# RJ45.net
KiCad netlist of a schematic drawn in Altium Designer
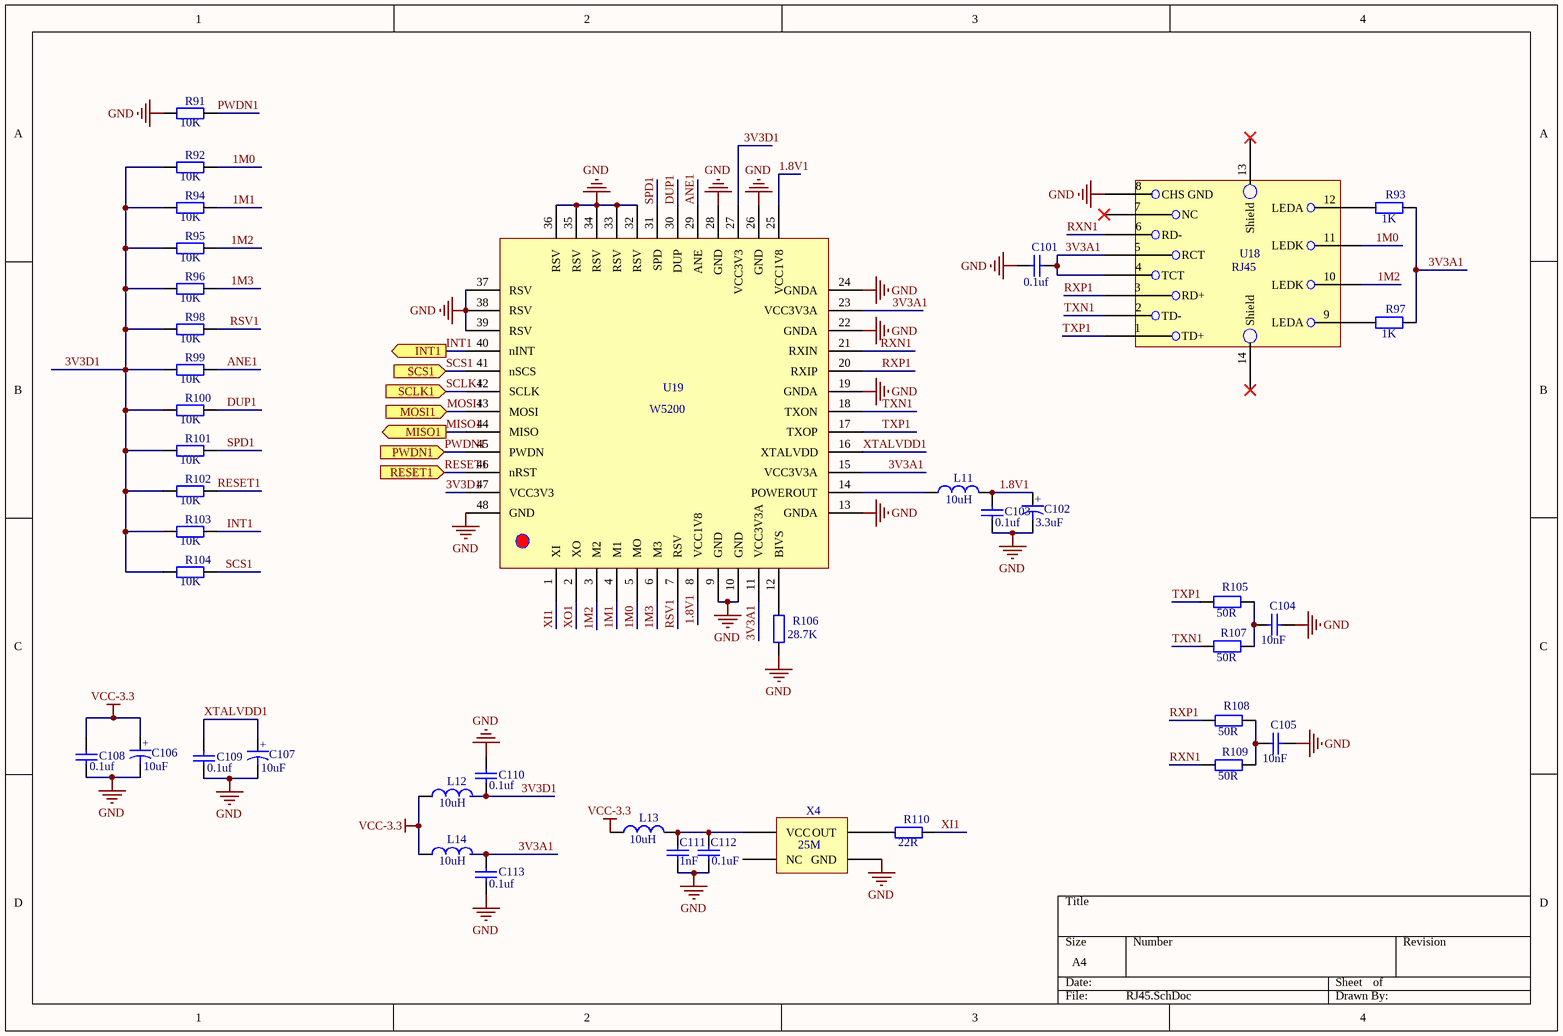
[diagram p0: RJ45.SchDoc]

(export (version "E")
  (design (tool "Eeschema 10.0.6"))
  (components
    (comp (ref "C101")
      (value "0.1uf")
      (footprint "0603")
      (fields (field (name "Comment") "Capacitor-0603"))
      (libsource (lib "原理图库") (part "Capacitor-0603"))
    )
    (comp (ref "C102")
      (value "3.3uF")
      (footprint "钽电容1206（A3216）")
      (fields (field (name "ALTIUM_UNNAMED_1") "+") (field (name "Comment") "电解电容"))
      (libsource (lib "原理图库") (part "电解电容"))
    )
    (comp (ref "C103")
      (value "0.1uf")
      (footprint "0603")
      (fields (field (name "Comment") "Capacitor-0603"))
      (libsource (lib "原理图库") (part "Capacitor-0603"))
    )
    (comp (ref "C104")
      (value "10nF")
      (footprint "0603")
      (fields (field (name "Comment") "Capacitor-0603"))
      (libsource (lib "原理图库") (part "Capacitor-0603"))
    )
    (comp (ref "C105")
      (value "10nF")
      (footprint "0603")
      (fields (field (name "Comment") "Capacitor-0603"))
      (libsource (lib "原理图库") (part "Capacitor-0603"))
    )
    (comp (ref "C106")
      (value "10uF")
      (footprint "钽电容1206（A3216）")
      (fields (field (name "ALTIUM_UNNAMED_1") "+") (field (name "Comment") "电解电容"))
      (libsource (lib "原理图库") (part "电解电容"))
    )
    (comp (ref "C107")
      (value "10uF")
      (footprint "钽电容1206（A3216）")
      (fields (field (name "ALTIUM_UNNAMED_1") "+") (field (name "Comment") "电解电容"))
      (libsource (lib "原理图库") (part "电解电容"))
    )
    (comp (ref "C108")
      (value "0.1uf")
      (footprint "0603")
      (fields (field (name "Comment") "Capacitor-0603"))
      (libsource (lib "原理图库") (part "Capacitor-0603"))
    )
    (comp (ref "C109")
      (value "0.1uf")
      (footprint "0603")
      (fields (field (name "Comment") "Capacitor-0603"))
      (libsource (lib "原理图库") (part "Capacitor-0603"))
    )
    (comp (ref "C110")
      (value "0.1uf")
      (footprint "0603")
      (fields (field (name "Comment") "Capacitor-0603"))
      (libsource (lib "原理图库") (part "Capacitor-0603"))
    )
    (comp (ref "C111")
      (value "1nF")
      (footprint "0603")
      (fields (field (name "Comment") "Capacitor-0603"))
      (libsource (lib "原理图库") (part "Capacitor-0603"))
    )
    (comp (ref "C112")
      (value "0.1uF")
      (footprint "0603")
      (fields (field (name "Comment") "Capacitor-0603"))
      (libsource (lib "原理图库") (part "Capacitor-0603"))
    )
    (comp (ref "C113")
      (value "0.1uf")
      (footprint "0603")
      (fields (field (name "Comment") "Capacitor-0603"))
      (libsource (lib "原理图库") (part "Capacitor-0603"))
    )
    (comp (ref "L11")
      (value "10uH")
      (footprint "0805")
      (fields (field (name "Comment") "Inductor"))
      (libsource (lib "原理图库") (part "Inductor"))
    )
    (comp (ref "L12")
      (value "10uH")
      (footprint "0805")
      (fields (field (name "Comment") "Inductor"))
      (libsource (lib "原理图库") (part "Inductor"))
    )
    (comp (ref "L13")
      (value "10uH")
      (footprint "0805")
      (fields (field (name "Comment") "Inductor"))
      (libsource (lib "原理图库") (part "Inductor"))
    )
    (comp (ref "L14")
      (value "10uH")
      (footprint "0805")
      (fields (field (name "Comment") "Inductor"))
      (libsource (lib "原理图库") (part "Inductor"))
    )
    (comp (ref "R91")
      (value "10K")
      (footprint "0603")
      (fields (field (name "Comment") "Resistor-0603"))
      (libsource (lib "原理图库") (part "Resistor-0603"))
    )
    (comp (ref "R92")
      (value "10K")
      (footprint "0603")
      (fields (field (name "Comment") "Resistor-0603"))
      (libsource (lib "原理图库") (part "Resistor-0603"))
    )
    (comp (ref "R93")
      (value "1K")
      (footprint "0603")
      (fields (field (name "Comment") "Resistor-0603"))
      (libsource (lib "原理图库") (part "Resistor-0603"))
    )
    (comp (ref "R94")
      (value "10K")
      (footprint "0603")
      (fields (field (name "Comment") "Resistor-0603"))
      (libsource (lib "原理图库") (part "Resistor-0603"))
    )
    (comp (ref "R95")
      (value "10K")
      (footprint "0603")
      (fields (field (name "Comment") "Resistor-0603"))
      (libsource (lib "原理图库") (part "Resistor-0603"))
    )
    (comp (ref "R96")
      (value "10K")
      (footprint "0603")
      (fields (field (name "Comment") "Resistor-0603"))
      (libsource (lib "原理图库") (part "Resistor-0603"))
    )
    (comp (ref "R97")
      (value "1K")
      (footprint "0603")
      (fields (field (name "Comment") "Resistor-0603"))
      (libsource (lib "原理图库") (part "Resistor-0603"))
    )
    (comp (ref "R98")
      (value "10K")
      (footprint "0603")
      (fields (field (name "Comment") "Resistor-0603"))
      (libsource (lib "原理图库") (part "Resistor-0603"))
    )
    (comp (ref "R99")
      (value "10K")
      (footprint "0603")
      (fields (field (name "Comment") "Resistor-0603"))
      (libsource (lib "原理图库") (part "Resistor-0603"))
    )
    (comp (ref "R100")
      (value "10K")
      (footprint "0603")
      (fields (field (name "Comment") "Resistor-0603"))
      (libsource (lib "原理图库") (part "Resistor-0603"))
    )
    (comp (ref "R101")
      (value "10K")
      (footprint "0603")
      (fields (field (name "Comment") "Resistor-0603"))
      (libsource (lib "原理图库") (part "Resistor-0603"))
    )
    (comp (ref "R102")
      (value "10K")
      (footprint "0603")
      (fields (field (name "Comment") "Resistor-0603"))
      (libsource (lib "原理图库") (part "Resistor-0603"))
    )
    (comp (ref "R103")
      (value "10K")
      (footprint "0603")
      (fields (field (name "Comment") "Resistor-0603"))
      (libsource (lib "原理图库") (part "Resistor-0603"))
    )
    (comp (ref "R104")
      (value "10K")
      (footprint "0603")
      (fields (field (name "Comment") "Resistor-0603"))
      (libsource (lib "原理图库") (part "Resistor-0603"))
    )
    (comp (ref "R105")
      (value "50R")
      (footprint "0603")
      (fields (field (name "Comment") "Resistor-0603"))
      (libsource (lib "原理图库") (part "Resistor-0603"))
    )
    (comp (ref "R106")
      (value "28.7K")
      (footprint "0603")
      (fields (field (name "Comment") "Resistor-0603"))
      (libsource (lib "") (part "Resistor-0603_1"))
    )
    (comp (ref "R107")
      (value "50R")
      (footprint "0603")
      (fields (field (name "Comment") "Resistor-0603"))
      (libsource (lib "原理图库") (part "Resistor-0603"))
    )
    (comp (ref "R108")
      (value "50R")
      (footprint "0603")
      (fields (field (name "Comment") "Resistor-0603"))
      (libsource (lib "原理图库") (part "Resistor-0603"))
    )
    (comp (ref "R109")
      (value "50R")
      (footprint "0603")
      (fields (field (name "Comment") "Resistor-0603"))
      (libsource (lib "原理图库") (part "Resistor-0603"))
    )
    (comp (ref "R110")
      (value "22R")
      (footprint "0603")
      (fields (field (name "Comment") "Resistor-0603"))
      (libsource (lib "原理图库") (part "Resistor-0603"))
    )
    (comp (ref "U18")
      (value "RJ45")
      (footprint "RJ45")
      (fields (field (name "NAME") "RJ45"))
      (libsource (lib "原理图库") (part "RJ45"))
    )
    (comp (ref "U19")
      (value "W5200-Chip")
      (footprint "W5200-Chip")
      (fields (field (name "NAME") "W5200"))
      (libsource (lib "原理图库") (part "W5200-Chip"))
    )
    (comp (ref "X4")
      (value "25M")
      (footprint "有源晶振7050")
      (fields (field (name "Comment") "有源晶振"))
      (libsource (lib "原理图库") (part "有源晶振"))
    )
  )
  (nets
    (net (code "1") (name "/1.8V1") (class "Default")
      (node (ref "C102") (pin "2") (pinfunction "2_2") (pintype "passive"))
      (node (ref "C103") (pin "2") (pinfunction "2_2") (pintype "passive"))
      (node (ref "L11") (pin "2") (pinfunction "2_2") (pintype "passive"))
      (node (ref "U19") (pin "25") (pinfunction "VCC1V8_25") (pintype "passive"))
      (node (ref "U19") (pin "8") (pinfunction "VCC1V8_8") (pintype "passive"))
    )
    (net (code "2") (name "/1M0") (class "Default")
      (node (ref "R92") (pin "2") (pinfunction "2_2") (pintype "passive"))
      (node (ref "U18") (pin "11") (pinfunction "LEDK_11") (pintype "passive"))
      (node (ref "U19") (pin "5") (pinfunction "MO_5") (pintype "passive"))
    )
    (net (code "3") (name "/1M1") (class "Default")
      (node (ref "R94") (pin "2") (pinfunction "2_2") (pintype "passive"))
      (node (ref "U19") (pin "4") (pinfunction "M1_4") (pintype "passive"))
    )
    (net (code "4") (name "/1M2") (class "Default")
      (node (ref "R95") (pin "2") (pinfunction "2_2") (pintype "passive"))
      (node (ref "U18") (pin "10") (pinfunction "LEDK_10") (pintype "passive"))
      (node (ref "U19") (pin "3") (pinfunction "M2_3") (pintype "passive"))
    )
    (net (code "5") (name "/1M3") (class "Default")
      (node (ref "R96") (pin "2") (pinfunction "2_2") (pintype "passive"))
      (node (ref "U19") (pin "6") (pinfunction "M3_6") (pintype "passive"))
    )
    (net (code "6") (name "/3V3A1") (class "Default")
      (node (ref "C101") (pin "1") (pinfunction "1_1") (pintype "passive"))
      (node (ref "C113") (pin "1") (pinfunction "1_1") (pintype "passive"))
      (node (ref "L14") (pin "2") (pinfunction "2_2") (pintype "passive"))
      (node (ref "R93") (pin "2") (pinfunction "2_2") (pintype "passive"))
      (node (ref "R97") (pin "2") (pinfunction "2_2") (pintype "passive"))
      (node (ref "U18") (pin "4") (pinfunction "TCT_4") (pintype "passive"))
      (node (ref "U18") (pin "5") (pinfunction "RCT_5") (pintype "passive"))
      (node (ref "U19") (pin "11") (pinfunction "VCC3V3A_11") (pintype "passive"))
      (node (ref "U19") (pin "15") (pinfunction "VCC3V3A_15") (pintype "passive"))
      (node (ref "U19") (pin "23") (pinfunction "VCC3V3A_23") (pintype "passive"))
    )
    (net (code "7") (name "/3V3D1") (class "Default")
      (node (ref "C110") (pin "1") (pinfunction "1_1") (pintype "passive"))
      (node (ref "L12") (pin "2") (pinfunction "2_2") (pintype "passive"))
      (node (ref "R100") (pin "1") (pinfunction "1_1") (pintype "passive"))
      (node (ref "R101") (pin "1") (pinfunction "1_1") (pintype "passive"))
      (node (ref "R102") (pin "1") (pinfunction "1_1") (pintype "passive"))
      (node (ref "R103") (pin "1") (pinfunction "1_1") (pintype "passive"))
      (node (ref "R104") (pin "1") (pinfunction "1_1") (pintype "passive"))
      (node (ref "R92") (pin "1") (pinfunction "1_1") (pintype "passive"))
      (node (ref "R94") (pin "1") (pinfunction "1_1") (pintype "passive"))
      (node (ref "R95") (pin "1") (pinfunction "1_1") (pintype "passive"))
      (node (ref "R96") (pin "1") (pinfunction "1_1") (pintype "passive"))
      (node (ref "R98") (pin "1") (pinfunction "1_1") (pintype "passive"))
      (node (ref "R99") (pin "1") (pinfunction "1_1") (pintype "passive"))
      (node (ref "U19") (pin "27") (pinfunction "VCC3V3_27") (pintype "passive"))
      (node (ref "U19") (pin "47") (pinfunction "VCC3V3_47") (pintype "passive"))
    )
    (net (code "8") (name "/ANE1") (class "Default")
      (node (ref "R99") (pin "2") (pinfunction "2_2") (pintype "passive"))
      (node (ref "U19") (pin "29") (pinfunction "ANE_29") (pintype "passive"))
    )
    (net (code "9") (name "/DUP1") (class "Default")
      (node (ref "R100") (pin "2") (pinfunction "2_2") (pintype "passive"))
      (node (ref "U19") (pin "30") (pinfunction "DUP_30") (pintype "passive"))
    )
    (net (code "10") (name "/INT1") (class "Default")
      (node (ref "R103") (pin "2") (pinfunction "2_2") (pintype "passive"))
      (node (ref "U19") (pin "40") (pinfunction "nINT_40") (pintype "passive"))
    )
    (net (code "11") (name "/MISO1") (class "Default")
      (node (ref "U19") (pin "44") (pinfunction "MISO_44") (pintype "passive"))
    )
    (net (code "12") (name "/MOSI1") (class "Default")
      (node (ref "U19") (pin "43") (pinfunction "MOSI_43") (pintype "passive"))
    )
    (net (code "13") (name "/PWDN1") (class "Default")
      (node (ref "R91") (pin "2") (pinfunction "2_2") (pintype "passive"))
      (node (ref "U19") (pin "45") (pinfunction "PWDN_45") (pintype "passive"))
    )
    (net (code "14") (name "/RESET1") (class "Default")
      (node (ref "R102") (pin "2") (pinfunction "2_2") (pintype "passive"))
      (node (ref "U19") (pin "46") (pinfunction "nRST_46") (pintype "passive"))
    )
    (net (code "15") (name "/RSV1") (class "Default")
      (node (ref "R98") (pin "2") (pinfunction "2_2") (pintype "passive"))
      (node (ref "U19") (pin "7") (pinfunction "RSV_7") (pintype "passive"))
    )
    (net (code "16") (name "/RXN1") (class "Default")
      (node (ref "R109") (pin "1") (pinfunction "1_1") (pintype "passive"))
      (node (ref "U18") (pin "6") (pinfunction "RD-_6") (pintype "passive"))
      (node (ref "U19") (pin "21") (pinfunction "RXIN_21") (pintype "passive"))
    )
    (net (code "17") (name "/RXP1") (class "Default")
      (node (ref "R108") (pin "1") (pinfunction "1_1") (pintype "passive"))
      (node (ref "U18") (pin "3") (pinfunction "RD+_3") (pintype "passive"))
      (node (ref "U19") (pin "20") (pinfunction "RXIP_20") (pintype "passive"))
    )
    (net (code "18") (name "/SCLK1") (class "Default")
      (node (ref "U19") (pin "42") (pinfunction "SCLK_42") (pintype "passive"))
    )
    (net (code "19") (name "/SCS1") (class "Default")
      (node (ref "R104") (pin "2") (pinfunction "2_2") (pintype "passive"))
      (node (ref "U19") (pin "41") (pinfunction "nSCS_41") (pintype "passive"))
    )
    (net (code "20") (name "/SPD1") (class "Default")
      (node (ref "R101") (pin "2") (pinfunction "2_2") (pintype "passive"))
      (node (ref "U19") (pin "31") (pinfunction "SPD_31") (pintype "passive"))
    )
    (net (code "21") (name "/TXN1") (class "Default")
      (node (ref "R107") (pin "1") (pinfunction "1_1") (pintype "passive"))
      (node (ref "U18") (pin "2") (pinfunction "TD-_2") (pintype "passive"))
      (node (ref "U19") (pin "18") (pinfunction "TXON_18") (pintype "passive"))
    )
    (net (code "22") (name "/TXP1") (class "Default")
      (node (ref "R105") (pin "1") (pinfunction "1_1") (pintype "passive"))
      (node (ref "U18") (pin "1") (pinfunction "TD+_1") (pintype "passive"))
      (node (ref "U19") (pin "17") (pinfunction "TXOP_17") (pintype "passive"))
    )
    (net (code "23") (name "/XI1") (class "Default")
      (node (ref "R110") (pin "2") (pinfunction "2_2") (pintype "passive"))
      (node (ref "U19") (pin "1") (pinfunction "XI_1") (pintype "passive"))
    )
    (net (code "24") (name "/XO1") (class "Default")
      (node (ref "U19") (pin "2") (pinfunction "XO_2") (pintype "passive"))
    )
    (net (code "25") (name "/XTALVDD1") (class "Default")
      (node (ref "C107") (pin "2") (pinfunction "2_2") (pintype "passive"))
      (node (ref "C109") (pin "2") (pinfunction "2_2") (pintype "passive"))
      (node (ref "U19") (pin "16") (pinfunction "XTALVDD_16") (pintype "passive"))
    )
    (net (code "26") (name "GND") (class "Default")
      (node (ref "C101") (pin "2") (pinfunction "2_2") (pintype "passive"))
      (node (ref "C102") (pin "1") (pinfunction "1_1") (pintype "passive"))
      (node (ref "C103") (pin "1") (pinfunction "1_1") (pintype "passive"))
      (node (ref "C104") (pin "2") (pinfunction "2_2") (pintype "passive"))
      (node (ref "C105") (pin "2") (pinfunction "2_2") (pintype "passive"))
      (node (ref "C106") (pin "1") (pinfunction "1_1") (pintype "passive"))
      (node (ref "C107") (pin "1") (pinfunction "1_1") (pintype "passive"))
      (node (ref "C108") (pin "1") (pinfunction "1_1") (pintype "passive"))
      (node (ref "C109") (pin "1") (pinfunction "1_1") (pintype "passive"))
      (node (ref "C110") (pin "2") (pinfunction "2_2") (pintype "passive"))
      (node (ref "C111") (pin "2") (pinfunction "2_2") (pintype "passive"))
      (node (ref "C112") (pin "2") (pinfunction "2_2") (pintype "passive"))
      (node (ref "C113") (pin "2") (pinfunction "2_2") (pintype "passive"))
      (node (ref "R106") (pin "1") (pinfunction "1_1") (pintype "passive"))
      (node (ref "R91") (pin "1") (pinfunction "1_1") (pintype "passive"))
      (node (ref "U18") (pin "8") (pinfunction "CHS_GND_8") (pintype "passive"))
      (node (ref "U19") (pin "10") (pinfunction "GND_10") (pintype "passive"))
      (node (ref "U19") (pin "13") (pinfunction "GNDA_13") (pintype "passive"))
      (node (ref "U19") (pin "19") (pinfunction "GNDA_19") (pintype "passive"))
      (node (ref "U19") (pin "22") (pinfunction "GNDA_22") (pintype "passive"))
      (node (ref "U19") (pin "24") (pinfunction "GNDA_24") (pintype "passive"))
      (node (ref "U19") (pin "26") (pinfunction "GND_26") (pintype "passive"))
      (node (ref "U19") (pin "28") (pinfunction "GND_28") (pintype "passive"))
      (node (ref "U19") (pin "32") (pinfunction "RSV_32") (pintype "passive"))
      (node (ref "U19") (pin "33") (pinfunction "RSV_33") (pintype "passive"))
      (node (ref "U19") (pin "34") (pinfunction "RSV_34") (pintype "passive"))
      (node (ref "U19") (pin "35") (pinfunction "RSV_35") (pintype "passive"))
      (node (ref "U19") (pin "36") (pinfunction "RSV_36") (pintype "passive"))
      (node (ref "U19") (pin "37") (pinfunction "RSV_37") (pintype "passive"))
      (node (ref "U19") (pin "38") (pinfunction "RSV_38") (pintype "passive"))
      (node (ref "U19") (pin "39") (pinfunction "RSV_39") (pintype "passive"))
      (node (ref "U19") (pin "48") (pinfunction "GND_48") (pintype "passive"))
      (node (ref "U19") (pin "9") (pinfunction "GND_9") (pintype "passive"))
      (node (ref "X4") (pin "2") (pinfunction "GND_2") (pintype "passive"))
    )
    (net (code "27") (name "Net-(C104-Pad1)") (class "Default")
      (node (ref "C104") (pin "1") (pinfunction "1_1") (pintype "passive"))
      (node (ref "R105") (pin "2") (pinfunction "2_2") (pintype "passive"))
      (node (ref "R107") (pin "2") (pinfunction "2_2") (pintype "passive"))
    )
    (net (code "28") (name "Net-(C105-Pad1)") (class "Default")
      (node (ref "C105") (pin "1") (pinfunction "1_1") (pintype "passive"))
      (node (ref "R108") (pin "2") (pinfunction "2_2") (pintype "passive"))
      (node (ref "R109") (pin "2") (pinfunction "2_2") (pintype "passive"))
    )
    (net (code "29") (name "Net-(R93-Pad1)") (class "Default")
      (node (ref "R93") (pin "1") (pinfunction "1_1") (pintype "passive"))
      (node (ref "U18") (pin "12") (pinfunction "LEDA_12") (pintype "passive"))
    )
    (net (code "30") (name "Net-(R97-Pad1)") (class "Default")
      (node (ref "R97") (pin "1") (pinfunction "1_1") (pintype "passive"))
      (node (ref "U18") (pin "9") (pinfunction "LEDA_9") (pintype "passive"))
    )
    (net (code "31") (name "Net-(U19-BIVS)") (class "Default")
      (node (ref "R106") (pin "2") (pinfunction "2_2") (pintype "passive"))
      (node (ref "U19") (pin "12") (pinfunction "BIVS_12") (pintype "passive"))
    )
    (net (code "32") (name "Net-(U19-POWEROUT)") (class "Default")
      (node (ref "L11") (pin "1") (pinfunction "1_1") (pintype "passive"))
      (node (ref "U19") (pin "14") (pinfunction "POWEROUT_14") (pintype "passive"))
    )
    (net (code "33") (name "Net-(X4-OUT)") (class "Default")
      (node (ref "R110") (pin "1") (pinfunction "1_1") (pintype "passive"))
      (node (ref "X4") (pin "3") (pinfunction "OUT_3") (pintype "passive"))
    )
    (net (code "34") (name "Net-(X4-VCC)") (class "Default")
      (node (ref "C111") (pin "1") (pinfunction "1_1") (pintype "passive"))
      (node (ref "C112") (pin "1") (pinfunction "1_1") (pintype "passive"))
      (node (ref "L13") (pin "2") (pinfunction "2_2") (pintype "passive"))
      (node (ref "X4") (pin "4") (pinfunction "VCC_4") (pintype "passive"))
    )
    (net (code "35") (name "VCC-3.3") (class "Default")
      (node (ref "C106") (pin "2") (pinfunction "2_2") (pintype "passive"))
      (node (ref "C108") (pin "2") (pinfunction "2_2") (pintype "passive"))
      (node (ref "L12") (pin "1") (pinfunction "1_1") (pintype "passive"))
      (node (ref "L13") (pin "1") (pinfunction "1_1") (pintype "passive"))
      (node (ref "L14") (pin "1") (pinfunction "1_1") (pintype "passive"))
    )
    (net (code "36") (name "unconnected-(U18-NC-Pad7)") (class "Default")
      (node (ref "U18") (pin "7") (pinfunction "NC_7") (pintype "passive+no_connect"))
    )
    (net (code "37") (name "unconnected-(U18-Shield-Pad13)") (class "Default")
      (node (ref "U18") (pin "13") (pinfunction "Shield_13") (pintype "passive+no_connect"))
    )
    (net (code "38") (name "unconnected-(U18-Shield-Pad14)") (class "Default")
      (node (ref "U18") (pin "14") (pinfunction "Shield_14") (pintype "passive+no_connect"))
    )
    (net (code "39") (name "unconnected-(X4-NC-Pad1)") (class "Default")
      (node (ref "X4") (pin "1") (pinfunction "NC_1") (pintype "passive"))
    )
  )
)
